# board_stm32.net
KiCad netlist of a schematic drawn in EAGLE
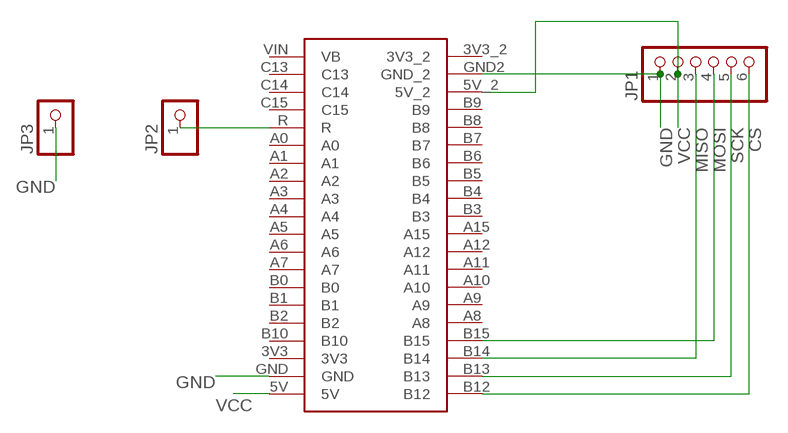
[diagram p0: schematic, sheet 1]

(export (version "E")
  (design (tool "Eeschema 10.0.6"))
  (components
    (comp (ref "JP1")
      (value "PINHD-1X6")
      (footprint "eagle-import:1X06")
      (libsource (lib "eagle-import") (part "PINHD-1X6"))
    )
    (comp (ref "JP2")
      (value "PINHD-1X1")
      (footprint "eagle-import:1X01")
      (libsource (lib "eagle-import") (part "PINHD-1X1"))
    )
    (comp (ref "JP3")
      (value "PINHD-1X1")
      (footprint "eagle-import:1X01")
      (libsource (lib "eagle-import") (part "PINHD-1X1"))
    )
    (comp (ref "U$1")
      (value "STM32F411CEU6")
      (footprint "eagle-import:STM32F411CEU6")
      (libsource (lib "eagle-import") (part "STM32F411CEU6"))
    )
  )
  (nets
    (net (code "1") (name "/CS") (class "Default")
      (node (ref "JP1") (pin "6") (pinfunction "6_6") (pintype "passive"))
      (node (ref "U$1") (pin "B12") (pinfunction "B12_B12") (pintype "bidirectional"))
    )
    (net (code "2") (name "/GND") (class "Default")
      (node (ref "JP1") (pin "1") (pinfunction "1_1") (pintype "passive"))
      (node (ref "JP3") (pin "1") (pinfunction "1_1") (pintype "passive"))
      (node (ref "U$1") (pin "GND") (pinfunction "GND_GND") (pintype "bidirectional"))
      (node (ref "U$1") (pin "GND2") (pinfunction "GND_2_GND2") (pintype "bidirectional"))
    )
    (net (code "3") (name "/MISO") (class "Default")
      (node (ref "JP1") (pin "3") (pinfunction "3_3") (pintype "passive"))
      (node (ref "U$1") (pin "B14") (pinfunction "B14_B14") (pintype "bidirectional"))
    )
    (net (code "4") (name "/MOSI") (class "Default")
      (node (ref "JP1") (pin "4") (pinfunction "4_4") (pintype "passive"))
      (node (ref "U$1") (pin "B15") (pinfunction "B15_B15") (pintype "bidirectional"))
    )
    (net (code "5") (name "/SCK") (class "Default")
      (node (ref "JP1") (pin "5") (pinfunction "5_5") (pintype "passive"))
      (node (ref "U$1") (pin "B13") (pinfunction "B13_B13") (pintype "bidirectional"))
    )
    (net (code "6") (name "/VCC") (class "Default")
      (node (ref "JP1") (pin "2") (pinfunction "2_2") (pintype "passive"))
      (node (ref "U$1") (pin "5V") (pinfunction "5V_5V") (pintype "bidirectional"))
      (node (ref "U$1") (pin "5V_2") (pinfunction "5V_2_5V_2") (pintype "bidirectional"))
    )
    (net (code "7") (name "Net-(JP2-Pad1)") (class "Default")
      (node (ref "JP2") (pin "1") (pinfunction "1_1") (pintype "passive"))
      (node (ref "U$1") (pin "R") (pinfunction "R_R") (pintype "bidirectional"))
    )
    (net (code "8") (name "unconnected-(U$1-Pad3V3)") (class "Default")
      (node (ref "U$1") (pin "3V3") (pinfunction "3V3_3V3") (pintype "bidirectional"))
    )
    (net (code "9") (name "unconnected-(U$1-Pad3V3_2)") (class "Default")
      (node (ref "U$1") (pin "3V3_2") (pinfunction "3V3_2_3V3_2") (pintype "bidirectional"))
    )
    (net (code "10") (name "unconnected-(U$1-PadA0)") (class "Default")
      (node (ref "U$1") (pin "A0") (pinfunction "A0_A0") (pintype "bidirectional"))
    )
    (net (code "11") (name "unconnected-(U$1-PadA1)") (class "Default")
      (node (ref "U$1") (pin "A1") (pinfunction "A1_A1") (pintype "bidirectional"))
    )
    (net (code "12") (name "unconnected-(U$1-PadA2)") (class "Default")
      (node (ref "U$1") (pin "A2") (pinfunction "A2_A2") (pintype "bidirectional"))
    )
    (net (code "13") (name "unconnected-(U$1-PadA3)") (class "Default")
      (node (ref "U$1") (pin "A3") (pinfunction "A3_A3") (pintype "bidirectional"))
    )
    (net (code "14") (name "unconnected-(U$1-PadA4)") (class "Default")
      (node (ref "U$1") (pin "A4") (pinfunction "A4_A4") (pintype "bidirectional"))
    )
    (net (code "15") (name "unconnected-(U$1-PadA5)") (class "Default")
      (node (ref "U$1") (pin "A5") (pinfunction "A5_A5") (pintype "bidirectional"))
    )
    (net (code "16") (name "unconnected-(U$1-PadA6)") (class "Default")
      (node (ref "U$1") (pin "A6") (pinfunction "A6_A6") (pintype "bidirectional"))
    )
    (net (code "17") (name "unconnected-(U$1-PadA7)") (class "Default")
      (node (ref "U$1") (pin "A7") (pinfunction "A7_A7") (pintype "bidirectional"))
    )
    (net (code "18") (name "unconnected-(U$1-PadA8)") (class "Default")
      (node (ref "U$1") (pin "A8") (pinfunction "A8_A8") (pintype "bidirectional"))
    )
    (net (code "19") (name "unconnected-(U$1-PadA9)") (class "Default")
      (node (ref "U$1") (pin "A9") (pinfunction "A9_A9") (pintype "bidirectional"))
    )
    (net (code "20") (name "unconnected-(U$1-PadA10)") (class "Default")
      (node (ref "U$1") (pin "A10") (pinfunction "A10_A10") (pintype "bidirectional"))
    )
    (net (code "21") (name "unconnected-(U$1-PadA11)") (class "Default")
      (node (ref "U$1") (pin "A11") (pinfunction "A11_A11") (pintype "bidirectional"))
    )
    (net (code "22") (name "unconnected-(U$1-PadA12)") (class "Default")
      (node (ref "U$1") (pin "A12") (pinfunction "A12_A12") (pintype "bidirectional"))
    )
    (net (code "23") (name "unconnected-(U$1-PadA15)") (class "Default")
      (node (ref "U$1") (pin "A15") (pinfunction "A15_A15") (pintype "bidirectional"))
    )
    (net (code "24") (name "unconnected-(U$1-PadB0)") (class "Default")
      (node (ref "U$1") (pin "B0") (pinfunction "B0_B0") (pintype "bidirectional"))
    )
    (net (code "25") (name "unconnected-(U$1-PadB1)") (class "Default")
      (node (ref "U$1") (pin "B1") (pinfunction "B1_B1") (pintype "bidirectional"))
    )
    (net (code "26") (name "unconnected-(U$1-PadB2)") (class "Default")
      (node (ref "U$1") (pin "B2") (pinfunction "B2_B2") (pintype "bidirectional"))
    )
    (net (code "27") (name "unconnected-(U$1-PadB3)") (class "Default")
      (node (ref "U$1") (pin "B3") (pinfunction "B3_B3") (pintype "bidirectional"))
    )
    (net (code "28") (name "unconnected-(U$1-PadB4)") (class "Default")
      (node (ref "U$1") (pin "B4") (pinfunction "B4_B4") (pintype "bidirectional"))
    )
    (net (code "29") (name "unconnected-(U$1-PadB5)") (class "Default")
      (node (ref "U$1") (pin "B5") (pinfunction "B5_B5") (pintype "bidirectional"))
    )
    (net (code "30") (name "unconnected-(U$1-PadB6)") (class "Default")
      (node (ref "U$1") (pin "B6") (pinfunction "B6_B6") (pintype "bidirectional"))
    )
    (net (code "31") (name "unconnected-(U$1-PadB7)") (class "Default")
      (node (ref "U$1") (pin "B7") (pinfunction "B7_B7") (pintype "bidirectional"))
    )
    (net (code "32") (name "unconnected-(U$1-PadB8)") (class "Default")
      (node (ref "U$1") (pin "B8") (pinfunction "B8_B8") (pintype "bidirectional"))
    )
    (net (code "33") (name "unconnected-(U$1-PadB9)") (class "Default")
      (node (ref "U$1") (pin "B9") (pinfunction "B9_B9") (pintype "bidirectional"))
    )
    (net (code "34") (name "unconnected-(U$1-PadB10)") (class "Default")
      (node (ref "U$1") (pin "B10") (pinfunction "B10_B10") (pintype "bidirectional"))
    )
    (net (code "35") (name "unconnected-(U$1-PadC13)") (class "Default")
      (node (ref "U$1") (pin "C13") (pinfunction "C13_C13") (pintype "bidirectional"))
    )
    (net (code "36") (name "unconnected-(U$1-PadC14)") (class "Default")
      (node (ref "U$1") (pin "C14") (pinfunction "C14_C14") (pintype "bidirectional"))
    )
    (net (code "37") (name "unconnected-(U$1-PadC15)") (class "Default")
      (node (ref "U$1") (pin "C15") (pinfunction "C15_C15") (pintype "bidirectional"))
    )
    (net (code "38") (name "unconnected-(U$1-VB-PadVIN)") (class "Default")
      (node (ref "U$1") (pin "VIN") (pinfunction "VB_VIN") (pintype "bidirectional"))
    )
  )
)
